# DPPXHK_10CL010_SDRAM.net
KiCad netlist of a schematic drawn in Altium Designer
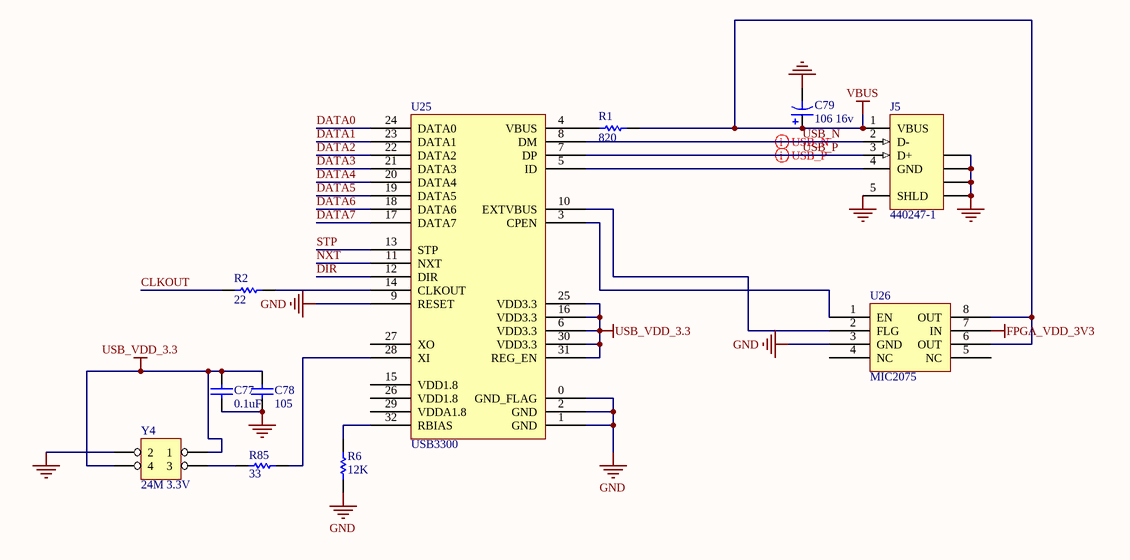
[diagram p0: DPPXHK_10CL010_SDRAM.SchDoc]

(export (version "E")
  (design (tool "Eeschema 10.0.6"))
  (components
    (comp (ref "C77")
      (value "0.1uF")
      (footprint "LC0402")
      (description "Capacitor (Semiconductor SIM Model)")
      (fields (field (name "Comment") "104") (field (name "PUBLISHER") "Altium Limited"))
      (libsource (lib "*") (part "Cap Semi"))
    )
    (comp (ref "C78")
      (value "105")
      (footprint "LC0402")
      (description "Capacitor (Semiconductor SIM Model)")
      (fields (field (name "PUBLISHER") "Altium Limited"))
      (libsource (lib "*") (part "Cap Semi"))
    )
    (comp (ref "C79")
      (value "106 16v")
      (footprint "LC0402")
      (description "Polarized Capacitor (Surface Mount)")
      (fields (field (name "PUBLISHER") "Altium Limited"))
      (libsource (lib "Miscellaneous Devices") (part "Cap Pol3"))
    )
    (comp (ref "J5")
      (value "440247-1")
      (footprint "MCRO_USB")
      (description "USB 2.0, Right Angle, SMT, B Type, Receptacle, 5 Position, Black")
      (fields (field (name "PUBLISHER") "Altium Limited"))
      (libsource (lib "AMP Serial Bus USB") (part "440247-1"))
    )
    (comp (ref "R1")
      (value "820")
      (footprint "0402R")
      (description "Resistor")
      (fields
        (field (name "MANUFACTURER") "Generic Components")
        (field (name "Comment") "10K")
        (field (name "PUBLISHER") "Altium Hobart Technology Centre")
      )
      (libsource (lib "*") (part "Res1"))
    )
    (comp (ref "R2")
      (value "22")
      (footprint "0402R")
      (description "Resistor")
      (fields
        (field (name "MANUFACTURER") "Generic Components")
        (field (name "Comment") "10K")
        (field (name "PUBLISHER") "Altium Hobart Technology Centre")
      )
      (libsource (lib "*") (part "Res1"))
    )
    (comp (ref "R6")
      (value "12K")
      (footprint "0402R")
      (description "Resistor")
      (fields
        (field (name "MANUFACTURER") "Generic Components")
        (field (name "Comment") "10K")
        (field (name "PUBLISHER") "Altium Hobart Technology Centre")
      )
      (libsource (lib "*") (part "Res1"))
    )
    (comp (ref "R85")
      (value "33")
      (footprint "0402R")
      (description "Resistor")
      (fields
        (field (name "MANUFACTURER") "Generic Components")
        (field (name "Comment") "33R")
        (field (name "PUBLISHER") "Altium Hobart Technology Centre")
      )
      (libsource (lib "*") (part "Res1"))
    )
    (comp (ref "U25") (value "USB3300") (footprint "QFN-32") (libsource (lib "PXHK") (part "USB3300")))
    (comp (ref "U26") (value "MIC2075") (footprint "SOIC-8") (libsource (lib "PXHK") (part "MIC2075")))
    (comp (ref "Y4")
      (value "24M 3.3V")
      (footprint "OSCILLATOR-3.2X2.5")
      (libsource (lib "*") (part "HEADER 2X2"))
    )
  )
  (nets
    (net (code "1") (name "/CLKOUT") (class "Default")
      (node (ref "R2") (pin "2") (pinfunction "2_2") (pintype "passive"))
    )
    (net (code "2") (name "/DATA0") (class "Default")
      (node (ref "U25") (pin "24") (pinfunction "DATA0_24") (pintype "passive"))
    )
    (net (code "3") (name "/DATA1") (class "Default")
      (node (ref "U25") (pin "23") (pinfunction "DATA1_23") (pintype "passive"))
    )
    (net (code "4") (name "/DATA2") (class "Default")
      (node (ref "U25") (pin "22") (pinfunction "DATA2_22") (pintype "passive"))
    )
    (net (code "5") (name "/DATA3") (class "Default")
      (node (ref "U25") (pin "21") (pinfunction "DATA3_21") (pintype "passive"))
    )
    (net (code "6") (name "/DATA4") (class "Default")
      (node (ref "U25") (pin "20") (pinfunction "DATA4_20") (pintype "passive"))
    )
    (net (code "7") (name "/DATA5") (class "Default")
      (node (ref "U25") (pin "19") (pinfunction "DATA5_19") (pintype "passive"))
    )
    (net (code "8") (name "/DATA6") (class "Default")
      (node (ref "U25") (pin "18") (pinfunction "DATA6_18") (pintype "passive"))
    )
    (net (code "9") (name "/DATA7") (class "Default")
      (node (ref "U25") (pin "17") (pinfunction "DATA7_17") (pintype "passive"))
    )
    (net (code "10") (name "/DIR") (class "Default")
      (node (ref "U25") (pin "12") (pinfunction "DIR_12") (pintype "passive"))
    )
    (net (code "11") (name "/NXT") (class "Default")
      (node (ref "U25") (pin "11") (pinfunction "NXT_11") (pintype "passive"))
    )
    (net (code "12") (name "/STP") (class "Default")
      (node (ref "U25") (pin "13") (pinfunction "STP_13") (pintype "passive"))
    )
    (net (code "13") (name "/USB_N") (class "Default")
      (node (ref "J5") (pin "2") (pinfunction "D-_2") (pintype "input"))
      (node (ref "U25") (pin "8") (pinfunction "DM_8") (pintype "passive"))
    )
    (net (code "14") (name "/USB_P") (class "Default")
      (node (ref "J5") (pin "3") (pinfunction "D+_3") (pintype "input"))
      (node (ref "U25") (pin "7") (pinfunction "DP_7") (pintype "passive"))
    )
    (net (code "15") (name "FPGA_VDD_3V3") (class "Default")
      (node (ref "U26") (pin "7") (pinfunction "IN_7") (pintype "passive"))
    )
    (net (code "16") (name "GND") (class "Default")
      (node (ref "C77") (pin "1") (pinfunction "1_1") (pintype "passive"))
      (node (ref "C78") (pin "1") (pinfunction "1_1") (pintype "passive"))
      (node (ref "C79") (pin "2") (pinfunction "2_2") (pintype "passive"))
      (node (ref "J5") (pin "5") (pinfunction "SHLD_5") (pintype "passive"))
      (node (ref "J5") (pin "6") (pinfunction "SHLD_6") (pintype "passive"))
      (node (ref "J5") (pin "7") (pinfunction "SHLD_7") (pintype "passive"))
      (node (ref "J5") (pin "8") (pinfunction "SHLD_8") (pintype "passive"))
      (node (ref "J5") (pin "9") (pinfunction "SHLD_9") (pintype "passive"))
      (node (ref "R6") (pin "1") (pinfunction "1_1") (pintype "passive"))
      (node (ref "U25") (pin "0") (pinfunction "GND_FLAG_0") (pintype "passive"))
      (node (ref "U25") (pin "1") (pinfunction "GND_1") (pintype "passive"))
      (node (ref "U25") (pin "2") (pinfunction "GND_2") (pintype "passive"))
      (node (ref "U25") (pin "9") (pinfunction "RESET_9") (pintype "passive"))
      (node (ref "U26") (pin "3") (pinfunction "GND_3") (pintype "passive"))
      (node (ref "Y4") (pin "2") (pinfunction "2_2") (pintype "passive"))
    )
    (net (code "17") (name "Net-(J5-GND)") (class "Default")
      (node (ref "J5") (pin "4") (pinfunction "GND_4") (pintype "power_in"))
      (node (ref "U25") (pin "5") (pinfunction "ID_5") (pintype "passive"))
    )
    (net (code "18") (name "Net-(R85-Pad1)") (class "Default")
      (node (ref "R85") (pin "1") (pinfunction "1_1") (pintype "passive"))
      (node (ref "Y4") (pin "3") (pinfunction "3_3") (pintype "passive"))
    )
    (net (code "19") (name "Net-(U25-CLKOUT)") (class "Default")
      (node (ref "R2") (pin "1") (pinfunction "1_1") (pintype "passive"))
      (node (ref "U25") (pin "14") (pinfunction "CLKOUT_14") (pintype "passive"))
    )
    (net (code "20") (name "Net-(U25-CPEN)") (class "Default")
      (node (ref "U25") (pin "3") (pinfunction "CPEN_3") (pintype "passive"))
      (node (ref "U26") (pin "1") (pinfunction "EN_1") (pintype "passive"))
    )
    (net (code "21") (name "Net-(U25-EXTVBUS)") (class "Default")
      (node (ref "U25") (pin "10") (pinfunction "EXTVBUS_10") (pintype "passive"))
      (node (ref "U26") (pin "2") (pinfunction "FLG_2") (pintype "passive"))
    )
    (net (code "22") (name "Net-(U25-RBIAS)") (class "Default")
      (node (ref "R6") (pin "2") (pinfunction "2_2") (pintype "passive"))
      (node (ref "U25") (pin "32") (pinfunction "RBIAS_32") (pintype "passive"))
    )
    (net (code "23") (name "Net-(U25-VBUS)") (class "Default")
      (node (ref "R1") (pin "2") (pinfunction "2_2") (pintype "passive"))
      (node (ref "U25") (pin "4") (pinfunction "VBUS_4") (pintype "passive"))
    )
    (net (code "24") (name "Net-(U25-XI)") (class "Default")
      (node (ref "R85") (pin "2") (pinfunction "2_2") (pintype "passive"))
      (node (ref "U25") (pin "28") (pinfunction "XI_28") (pintype "passive"))
    )
    (net (code "25") (name "USB_VDD_3.3") (class "Default")
      (node (ref "C77") (pin "2") (pinfunction "2_2") (pintype "passive"))
      (node (ref "C78") (pin "2") (pinfunction "2_2") (pintype "passive"))
      (node (ref "U25") (pin "16") (pinfunction "VDD3.3_16") (pintype "passive"))
      (node (ref "U25") (pin "25") (pinfunction "VDD3.3_25") (pintype "passive"))
      (node (ref "U25") (pin "30") (pinfunction "VDD3.3_30") (pintype "passive"))
      (node (ref "U25") (pin "31") (pinfunction "REG_EN_31") (pintype "passive"))
      (node (ref "U25") (pin "6") (pinfunction "VDD3.3_6") (pintype "passive"))
      (node (ref "Y4") (pin "1") (pinfunction "1_1") (pintype "passive"))
      (node (ref "Y4") (pin "4") (pinfunction "4_4") (pintype "passive"))
    )
    (net (code "26") (name "VBUS") (class "Default")
      (node (ref "C79") (pin "1") (pinfunction "1_1") (pintype "passive"))
      (node (ref "J5") (pin "1") (pinfunction "VBUS_1") (pintype "power_in"))
      (node (ref "R1") (pin "1") (pinfunction "1_1") (pintype "passive"))
      (node (ref "U26") (pin "6") (pinfunction "OUT_6") (pintype "passive"))
      (node (ref "U26") (pin "8") (pinfunction "OUT_8") (pintype "passive"))
    )
    (net (code "27") (name "unconnected-(U25-VDD1.8-Pad15)") (class "Default")
      (node (ref "U25") (pin "15") (pinfunction "VDD1.8_15") (pintype "passive"))
    )
    (net (code "28") (name "unconnected-(U25-VDD1.8-Pad26)") (class "Default")
      (node (ref "U25") (pin "26") (pinfunction "VDD1.8_26") (pintype "passive"))
    )
    (net (code "29") (name "unconnected-(U25-VDDA1.8-Pad29)") (class "Default")
      (node (ref "U25") (pin "29") (pinfunction "VDDA1.8_29") (pintype "passive"))
    )
    (net (code "30") (name "unconnected-(U25-XO-Pad27)") (class "Default")
      (node (ref "U25") (pin "27") (pinfunction "XO_27") (pintype "passive"))
    )
    (net (code "31") (name "unconnected-(U26-NC-Pad4)") (class "Default")
      (node (ref "U26") (pin "4") (pinfunction "NC_4") (pintype "passive"))
    )
    (net (code "32") (name "unconnected-(U26-NC-Pad5)") (class "Default")
      (node (ref "U26") (pin "5") (pinfunction "NC_5") (pintype "passive"))
    )
  )
)
